# minireg-tps560430.net
KiCad netlist of a schematic drawn in Altium Designer
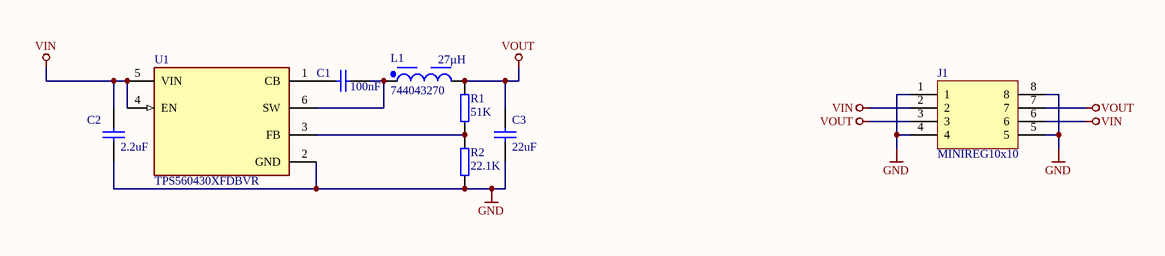
[diagram p0: minireg-tps560430.SchDoc]

(export (version "E")
  (design (tool "Eeschema 10.0.6"))
  (components
    (comp (ref "C1")
      (value "100nF")
      (footprint "CAP0603")
      (description "CAP SM 0603 X7R 100nF")
      (fields (field (name "PART NUMBER") "CAP-SM-0603-X7R-100nF") (field (name "MANUFACTURER") "GENERIC"))
      (libsource (lib "electronpowered") (part "CAP"))
    )
    (comp (ref "C2")
      (value "2.2uF")
      (footprint "CAP0603")
      (description "CAP SM 0603 X5R 2.2uF")
      (fields (field (name "PART NUMBER") "CAP-SM-0603-X5R-2.2uF") (field (name "MANUFACTURER") "GENERIC"))
      (libsource (lib "electronpowered") (part "CAP"))
    )
    (comp (ref "C3")
      (value "22uF")
      (footprint "CAP0805")
      (description "CAP SM 0805 X5R 22uF")
      (fields (field (name "PART NUMBER") "CAP-SM-0805-X5R-22uF") (field (name "MANUFACTURER") "GENERIC"))
      (libsource (lib "electronpowered") (part "CAP"))
    )
    (comp (ref "J1")
      (value "MINIREG10x10")
      (footprint "MINIREG8_10x10R")
      (libsource (lib "minireg") (part "MINIREG10x10"))
    )
    (comp (ref "L1")
      (value "744043270")
      (footprint "WE-TPC_4828")
      (fields (field (name "INDUCTANCE") "27µH"))
      (libsource (lib "minireg") (part "744043270"))
    )
    (comp (ref "R1")
      (value "51K")
      (footprint "RES0603")
      (description "RES SM 0603 51K")
      (fields (field (name "PART NUMBER") "RES-SM-0603-51K") (field (name "MANUFACTURER") "GENERIC"))
      (libsource (lib "electronpowered") (part "RES"))
    )
    (comp (ref "R2")
      (value "22.1K")
      (footprint "RES0603")
      (description "RES SM 0603 22.1K")
      (fields (field (name "PART NUMBER") "RES-SM-0603-22.1K") (field (name "MANUFACTURER") "GENERIC"))
      (libsource (lib "electronpowered") (part "RES"))
    )
    (comp (ref "U1")
      (value "TPS560430XFDBVR")
      (footprint "minireg:FP-DBV0006A-IPC_C")
      (description "IC REG BUCK PWM 600MA SOT23-6")
      (libsource (lib "minireg") (part "TPS560430XFDBVR"))
    )
  )
  (nets
    (net (code "1") (name "GND") (class "Default")
      (node (ref "C2") (pin "1") (pinfunction "1_1") (pintype "passive"))
      (node (ref "C3") (pin "1") (pinfunction "1_1") (pintype "passive"))
      (node (ref "J1") (pin "1") (pinfunction "1_1") (pintype "power_in"))
      (node (ref "J1") (pin "4") (pinfunction "4_4") (pintype "power_in"))
      (node (ref "J1") (pin "5") (pinfunction "5_5") (pintype "power_in"))
      (node (ref "J1") (pin "8") (pinfunction "8_8") (pintype "power_in"))
      (node (ref "R2") (pin "1") (pinfunction "1_1") (pintype "passive"))
      (node (ref "U1") (pin "2") (pinfunction "GND_2") (pintype "power_in"))
    )
    (net (code "2") (name "Net-(U1-CB)") (class "Default")
      (node (ref "C1") (pin "1") (pinfunction "1_1") (pintype "passive"))
      (node (ref "U1") (pin "1") (pinfunction "CB_1") (pintype "passive"))
    )
    (net (code "3") (name "Net-(U1-FB)") (class "Default")
      (node (ref "R1") (pin "1") (pinfunction "1_1") (pintype "passive"))
      (node (ref "R2") (pin "2") (pinfunction "2_2") (pintype "passive"))
      (node (ref "U1") (pin "3") (pinfunction "FB_3") (pintype "passive"))
    )
    (net (code "4") (name "Net-(U1-SW)") (class "Default")
      (node (ref "C1") (pin "2") (pinfunction "2_2") (pintype "passive"))
      (node (ref "L1") (pin "1") (pinfunction "1_1") (pintype "passive"))
      (node (ref "U1") (pin "6") (pinfunction "SW_6") (pintype "passive"))
    )
    (net (code "5") (name "VIN") (class "Default")
      (node (ref "C2") (pin "2") (pinfunction "2_2") (pintype "passive"))
      (node (ref "J1") (pin "2") (pinfunction "2_2") (pintype "power_in"))
      (node (ref "J1") (pin "6") (pinfunction "6_6") (pintype "power_in"))
      (node (ref "U1") (pin "4") (pinfunction "EN_4") (pintype "input"))
      (node (ref "U1") (pin "5") (pinfunction "VIN_5") (pintype "power_in"))
    )
    (net (code "6") (name "VOUT") (class "Default")
      (node (ref "C3") (pin "2") (pinfunction "2_2") (pintype "passive"))
      (node (ref "J1") (pin "3") (pinfunction "3_3") (pintype "power_in"))
      (node (ref "J1") (pin "7") (pinfunction "7_7") (pintype "power_in"))
      (node (ref "L1") (pin "2") (pinfunction "2_2") (pintype "passive"))
      (node (ref "R1") (pin "2") (pinfunction "2_2") (pintype "passive"))
    )
  )
)
